# ecmeter.net
KiCad netlist of a schematic drawn in EAGLE
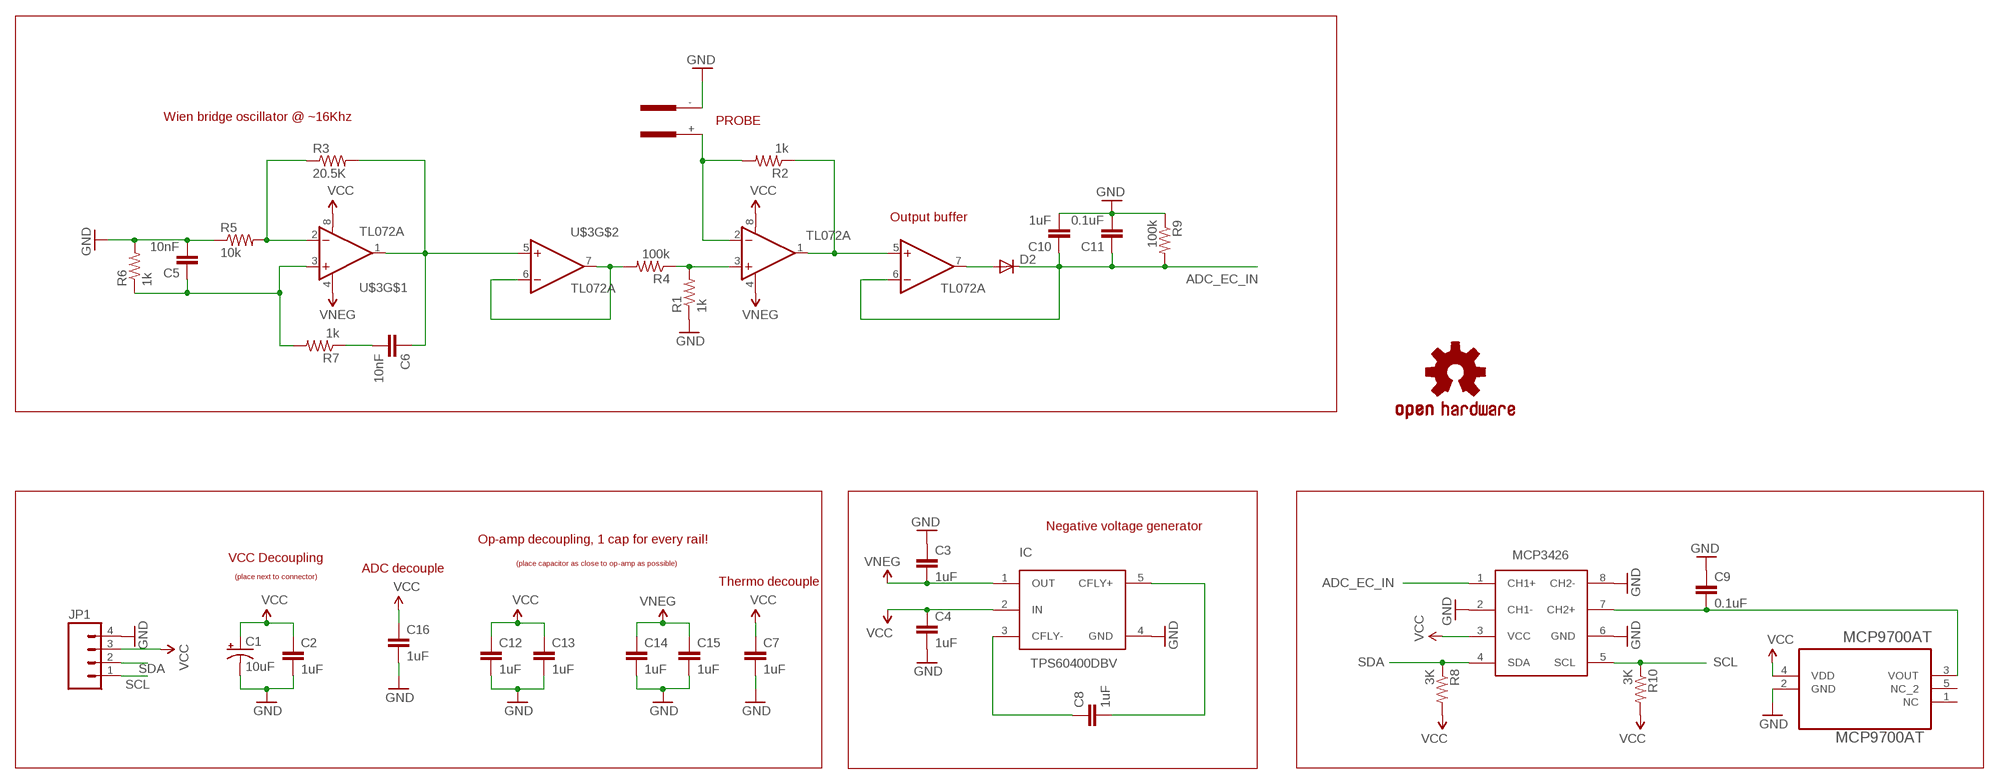
[diagram p0: schematic, sheet 1]

(export (version "E")
  (design (tool "Eeschema 10.0.6"))
  (components
    (comp (ref "C1")
      (value "10uF")
      (footprint "eagle-import:EIA3216")
      (libsource (lib "eagle-import") (part "10UF-TANT"))
    )
    (comp (ref "C2")
      (value "1uF")
      (footprint "eagle-import:0805")
      (libsource (lib "eagle-import") (part "CAP0805"))
    )
    (comp (ref "C3")
      (value "1uF")
      (footprint "eagle-import:0805")
      (libsource (lib "eagle-import") (part "CAP0805"))
    )
    (comp (ref "C4")
      (value "1uF")
      (footprint "eagle-import:0805")
      (libsource (lib "eagle-import") (part "CAP0805"))
    )
    (comp (ref "C5")
      (value "10nF")
      (footprint "eagle-import:0603-CAP")
      (libsource (lib "eagle-import") (part "CAP0603-CAP"))
    )
    (comp (ref "C6")
      (value "10nF")
      (footprint "eagle-import:0603-CAP")
      (libsource (lib "eagle-import") (part "CAP0603-CAP"))
    )
    (comp (ref "C7")
      (value "1uF")
      (footprint "eagle-import:0805")
      (libsource (lib "eagle-import") (part "CAP0805"))
    )
    (comp (ref "C8")
      (value "1uF")
      (footprint "eagle-import:0805")
      (libsource (lib "eagle-import") (part "CAP0805"))
    )
    (comp (ref "C9")
      (value "0.1uF")
      (footprint "eagle-import:0805")
      (libsource (lib "eagle-import") (part "CAP0805"))
    )
    (comp (ref "C10")
      (value "1uF")
      (footprint "eagle-import:0805")
      (libsource (lib "eagle-import") (part "CAP0805"))
    )
    (comp (ref "C11")
      (value "0.1uF")
      (footprint "eagle-import:0805")
      (libsource (lib "eagle-import") (part "CAP0805"))
    )
    (comp (ref "C12")
      (value "1uF")
      (footprint "eagle-import:0805")
      (libsource (lib "eagle-import") (part "CAP0805"))
    )
    (comp (ref "C13")
      (value "1uF")
      (footprint "eagle-import:0805")
      (libsource (lib "eagle-import") (part "CAP0805"))
    )
    (comp (ref "C14")
      (value "1uF")
      (footprint "eagle-import:0805")
      (libsource (lib "eagle-import") (part "CAP0805"))
    )
    (comp (ref "C15")
      (value "1uF")
      (footprint "eagle-import:0805")
      (libsource (lib "eagle-import") (part "CAP0805"))
    )
    (comp (ref "C16")
      (value "1uF")
      (footprint "eagle-import:0805")
      (libsource (lib "eagle-import") (part "CAP0805"))
    )
    (comp (ref "D2")
      (value "DIODESOD")
      (footprint "eagle-import:SOD-323")
      (libsource (lib "eagle-import") (part "DIODESOD"))
    )
    (comp (ref "IC")
      (value "TPS60400DBV")
      (footprint "eagle-import:SOT23-5")
      (libsource (lib "eagle-import") (part "TPS60400DBV"))
    )
    (comp (ref "JP1")
      (value "M04POLAR")
      (footprint "eagle-import:MOLEX-1X4")
      (libsource (lib "eagle-import") (part "M04POLAR"))
    )
    (comp (ref "LOGO1")
      (value "OSHW-LOGOM")
      (footprint "eagle-import:OSHW-LOGO-M")
      (libsource (lib "eagle-import") (part "OSHW-LOGOM"))
    )
    (comp (ref "MCP9700AT")
      (value "MCP9700AT")
      (footprint "eagle-import:SOT65P210X110-5N")
      (fields (field (name "MPN") "MCP9700AT-E/LT"))
      (libsource (lib "eagle-import") (part "MCP9700AT-E/LT"))
    )
    (comp (ref "R1")
      (value "1k")
      (footprint "eagle-import:0603-RES")
      (libsource (lib "eagle-import") (part "1K-1%"))
    )
    (comp (ref "R2")
      (value "1k")
      (footprint "eagle-import:0603-RES")
      (libsource (lib "eagle-import") (part "1K-1%"))
    )
    (comp (ref "R3")
      (value "20.5K")
      (footprint "eagle-import:0603-RES")
      (libsource (lib "eagle-import") (part "22KOHM1/10W1%(0603)"))
    )
    (comp (ref "R4")
      (value "100k")
      (footprint "eagle-import:0603-RES")
      (libsource (lib "eagle-import") (part "1K-1%"))
    )
    (comp (ref "R5")
      (value "10k")
      (footprint "eagle-import:0603-RES")
      (libsource (lib "eagle-import") (part "10K-1%RES-00824"))
    )
    (comp (ref "R6")
      (value "1k")
      (footprint "eagle-import:0603-RES")
      (libsource (lib "eagle-import") (part "1K-1%"))
    )
    (comp (ref "R7")
      (value "1k")
      (footprint "eagle-import:0603-RES")
      (libsource (lib "eagle-import") (part "1K-1%"))
    )
    (comp (ref "R8")
      (value "3K")
      (footprint "eagle-import:0603-RES")
      (libsource (lib "eagle-import") (part "10K-1%RES-00824"))
    )
    (comp (ref "R9")
      (value "100k")
      (footprint "eagle-import:0603-RES")
      (libsource (lib "eagle-import") (part "10K-1%RES-00824"))
    )
    (comp (ref "R10")
      (value "3K")
      (footprint "eagle-import:0603-RES")
      (libsource (lib "eagle-import") (part "10K-1%RES-00824"))
    )
    (comp (ref "U$1")
      (value "TL072A")
      (footprint "eagle-import:SOIC8")
      (libsource (lib "eagle-import") (part "TL072A"))
    )
    (comp (ref "U$2")
      (value "K1-PROBE")
      (footprint "eagle-import:K1-PROBE")
      (libsource (lib "eagle-import") (part "K1-PROBE"))
    )
    (comp (ref "U$3")
      (value "TL072A")
      (footprint "eagle-import:SOIC8")
      (libsource (lib "eagle-import") (part "TL072A"))
    )
    (comp (ref "U$4")
      (value "MCP3426")
      (footprint "eagle-import:SOIC8")
      (libsource (lib "eagle-import") (part "MCP3426"))
    )
  )
  (nets
    (net (code "1") (name "/ADC_EC_IN") (class "Default")
      (node (ref "C10") (pin "1") (pinfunction "1_1") (pintype "passive"))
      (node (ref "C11") (pin "1") (pinfunction "1_1") (pintype "passive"))
      (node (ref "D2") (pin "1") (pinfunction "C_1") (pintype "passive"))
      (node (ref "R9") (pin "2") (pinfunction "2_2") (pintype "passive"))
      (node (ref "U$1") (pin "6") (pinfunction "-IN_6") (pintype "input"))
      (node (ref "U$4") (pin "1") (pinfunction "CH1+_1") (pintype "bidirectional"))
    )
    (net (code "2") (name "/SCL") (class "Default")
      (node (ref "JP1") (pin "1") (pinfunction "1_1") (pintype "passive"))
      (node (ref "R10") (pin "1") (pinfunction "1_1") (pintype "passive"))
      (node (ref "U$4") (pin "5") (pinfunction "SCL_5") (pintype "bidirectional"))
    )
    (net (code "3") (name "/SDA") (class "Default")
      (node (ref "JP1") (pin "2") (pinfunction "2_2") (pintype "passive"))
      (node (ref "R8") (pin "1") (pinfunction "1_1") (pintype "passive"))
      (node (ref "U$4") (pin "4") (pinfunction "SDA_4") (pintype "bidirectional"))
    )
    (net (code "4") (name "GND") (class "Default")
      (node (ref "C1") (pin "C") (pinfunction "-_C") (pintype "passive"))
      (node (ref "C10") (pin "2") (pinfunction "2_2") (pintype "passive"))
      (node (ref "C11") (pin "2") (pinfunction "2_2") (pintype "passive"))
      (node (ref "C12") (pin "2") (pinfunction "2_2") (pintype "passive"))
      (node (ref "C13") (pin "2") (pinfunction "2_2") (pintype "passive"))
      (node (ref "C14") (pin "2") (pinfunction "2_2") (pintype "passive"))
      (node (ref "C15") (pin "2") (pinfunction "2_2") (pintype "passive"))
      (node (ref "C16") (pin "2") (pinfunction "2_2") (pintype "passive"))
      (node (ref "C2") (pin "2") (pinfunction "2_2") (pintype "passive"))
      (node (ref "C3") (pin "1") (pinfunction "1_1") (pintype "passive"))
      (node (ref "C4") (pin "2") (pinfunction "2_2") (pintype "passive"))
      (node (ref "C5") (pin "2") (pinfunction "2_2") (pintype "passive"))
      (node (ref "C7") (pin "2") (pinfunction "2_2") (pintype "passive"))
      (node (ref "C9") (pin "1") (pinfunction "1_1") (pintype "passive"))
      (node (ref "IC") (pin "4") (pinfunction "GND_4") (pintype "bidirectional"))
      (node (ref "JP1") (pin "4") (pinfunction "4_4") (pintype "passive"))
      (node (ref "MCP9700AT") (pin "2") (pinfunction "GND_2") (pintype "passive"))
      (node (ref "R1") (pin "1") (pinfunction "1_1") (pintype "passive"))
      (node (ref "R5") (pin "1") (pinfunction "1_1") (pintype "passive"))
      (node (ref "R6") (pin "2") (pinfunction "2_2") (pintype "passive"))
      (node (ref "R9") (pin "1") (pinfunction "1_1") (pintype "passive"))
      (node (ref "U$2") (pin "-") (pinfunction "P$2_-") (pintype "bidirectional"))
      (node (ref "U$4") (pin "2") (pinfunction "CH1-_2") (pintype "bidirectional"))
      (node (ref "U$4") (pin "6") (pinfunction "GND_6") (pintype "bidirectional"))
      (node (ref "U$4") (pin "8") (pinfunction "CH2-_8") (pintype "bidirectional"))
    )
    (net (code "5") (name "Net-(C6-Pad2)") (class "Default")
      (node (ref "C6") (pin "2") (pinfunction "2_2") (pintype "passive"))
      (node (ref "R7") (pin "1") (pinfunction "1_1") (pintype "passive"))
    )
    (net (code "6") (name "Net-(D2-A)") (class "Default")
      (node (ref "D2") (pin "2") (pinfunction "A_2") (pintype "passive"))
      (node (ref "U$1") (pin "7") (pinfunction "OUT_7") (pintype "output"))
    )
    (net (code "7") (name "Net-(IC-CFLY+)") (class "Default")
      (node (ref "C8") (pin "2") (pinfunction "2_2") (pintype "passive"))
      (node (ref "IC") (pin "5") (pinfunction "CFLY+_5") (pintype "bidirectional"))
    )
    (net (code "8") (name "Net-(IC-CFLY-)") (class "Default")
      (node (ref "C8") (pin "1") (pinfunction "1_1") (pintype "passive"))
      (node (ref "IC") (pin "3") (pinfunction "CFLY-_3") (pintype "bidirectional"))
    )
    (net (code "9") (name "Net-(MCP9700AT-VOUT)") (class "Default")
      (node (ref "C9") (pin "2") (pinfunction "2_2") (pintype "passive"))
      (node (ref "MCP9700AT") (pin "3") (pinfunction "VOUT_3") (pintype "output"))
      (node (ref "U$4") (pin "7") (pinfunction "CH2+_7") (pintype "bidirectional"))
    )
    (net (code "10") (name "Net-(U$1A-+IN)") (class "Default")
      (node (ref "R1") (pin "2") (pinfunction "2_2") (pintype "passive"))
      (node (ref "R4") (pin "1") (pinfunction "1_1") (pintype "passive"))
      (node (ref "U$1") (pin "3") (pinfunction "+IN_3") (pintype "input"))
    )
    (net (code "11") (name "Net-(U$1A--IN)") (class "Default")
      (node (ref "R2") (pin "2") (pinfunction "2_2") (pintype "passive"))
      (node (ref "U$1") (pin "2") (pinfunction "-IN_2") (pintype "input"))
      (node (ref "U$2") (pin "+") (pinfunction "P$1_+") (pintype "bidirectional"))
    )
    (net (code "12") (name "Net-(U$1A-OUT)") (class "Default")
      (node (ref "R2") (pin "1") (pinfunction "1_1") (pintype "passive"))
      (node (ref "U$1") (pin "1") (pinfunction "OUT_1") (pintype "output"))
      (node (ref "U$1") (pin "5") (pinfunction "+IN_5") (pintype "input"))
    )
    (net (code "13") (name "Net-(U$3A-+IN)") (class "Default")
      (node (ref "C5") (pin "1") (pinfunction "1_1") (pintype "passive"))
      (node (ref "R6") (pin "1") (pinfunction "1_1") (pintype "passive"))
      (node (ref "R7") (pin "2") (pinfunction "2_2") (pintype "passive"))
      (node (ref "U$3") (pin "3") (pinfunction "+IN_3") (pintype "input"))
    )
    (net (code "14") (name "Net-(U$3A--IN)") (class "Default")
      (node (ref "R3") (pin "1") (pinfunction "1_1") (pintype "passive"))
      (node (ref "R5") (pin "2") (pinfunction "2_2") (pintype "passive"))
      (node (ref "U$3") (pin "2") (pinfunction "-IN_2") (pintype "input"))
    )
    (net (code "15") (name "Net-(U$3A-OUT)") (class "Default")
      (node (ref "C6") (pin "1") (pinfunction "1_1") (pintype "passive"))
      (node (ref "R3") (pin "2") (pinfunction "2_2") (pintype "passive"))
      (node (ref "U$3") (pin "1") (pinfunction "OUT_1") (pintype "output"))
      (node (ref "U$3") (pin "5") (pinfunction "+IN_5") (pintype "input"))
    )
    (net (code "16") (name "Net-(U$3B--IN)") (class "Default")
      (node (ref "R4") (pin "2") (pinfunction "2_2") (pintype "passive"))
      (node (ref "U$3") (pin "6") (pinfunction "-IN_6") (pintype "input"))
      (node (ref "U$3") (pin "7") (pinfunction "OUT_7") (pintype "output"))
    )
    (net (code "17") (name "VCC") (class "Default")
      (node (ref "C1") (pin "A") (pinfunction "+_A") (pintype "passive"))
      (node (ref "C12") (pin "1") (pinfunction "1_1") (pintype "passive"))
      (node (ref "C13") (pin "1") (pinfunction "1_1") (pintype "passive"))
      (node (ref "C16") (pin "1") (pinfunction "1_1") (pintype "passive"))
      (node (ref "C2") (pin "1") (pinfunction "1_1") (pintype "passive"))
      (node (ref "C4") (pin "1") (pinfunction "1_1") (pintype "passive"))
      (node (ref "C7") (pin "1") (pinfunction "1_1") (pintype "passive"))
      (node (ref "IC") (pin "2") (pinfunction "IN_2") (pintype "bidirectional"))
      (node (ref "JP1") (pin "3") (pinfunction "3_3") (pintype "passive"))
      (node (ref "MCP9700AT") (pin "4") (pinfunction "VDD_4") (pintype "power_in"))
      (node (ref "R10") (pin "2") (pinfunction "2_2") (pintype "passive"))
      (node (ref "R8") (pin "2") (pinfunction "2_2") (pintype "passive"))
      (node (ref "U$1") (pin "8") (pinfunction "V+_8") (pintype "power_in"))
      (node (ref "U$3") (pin "8") (pinfunction "V+_8") (pintype "power_in"))
      (node (ref "U$4") (pin "3") (pinfunction "VCC_3") (pintype "bidirectional"))
    )
    (net (code "18") (name "VNEG") (class "Default")
      (node (ref "C14") (pin "1") (pinfunction "1_1") (pintype "passive"))
      (node (ref "C15") (pin "1") (pinfunction "1_1") (pintype "passive"))
      (node (ref "C3") (pin "2") (pinfunction "2_2") (pintype "passive"))
      (node (ref "IC") (pin "1") (pinfunction "OUT_1") (pintype "bidirectional"))
      (node (ref "U$1") (pin "4") (pinfunction "V-_4") (pintype "power_in"))
      (node (ref "U$3") (pin "4") (pinfunction "V-_4") (pintype "power_in"))
    )
    (net (code "19") (name "unconnected-(MCP9700AT-NC-Pad1)") (class "Default")
      (node (ref "MCP9700AT") (pin "1") (pinfunction "NC_1") (pintype "no_connect"))
    )
    (net (code "20") (name "unconnected-(MCP9700AT-NC_2-Pad5)") (class "Default")
      (node (ref "MCP9700AT") (pin "5") (pinfunction "NC_2_5") (pintype "no_connect"))
    )
  )
)
